# Ultrasonic_mbed.net
KiCad netlist of a schematic drawn in Altium Designer
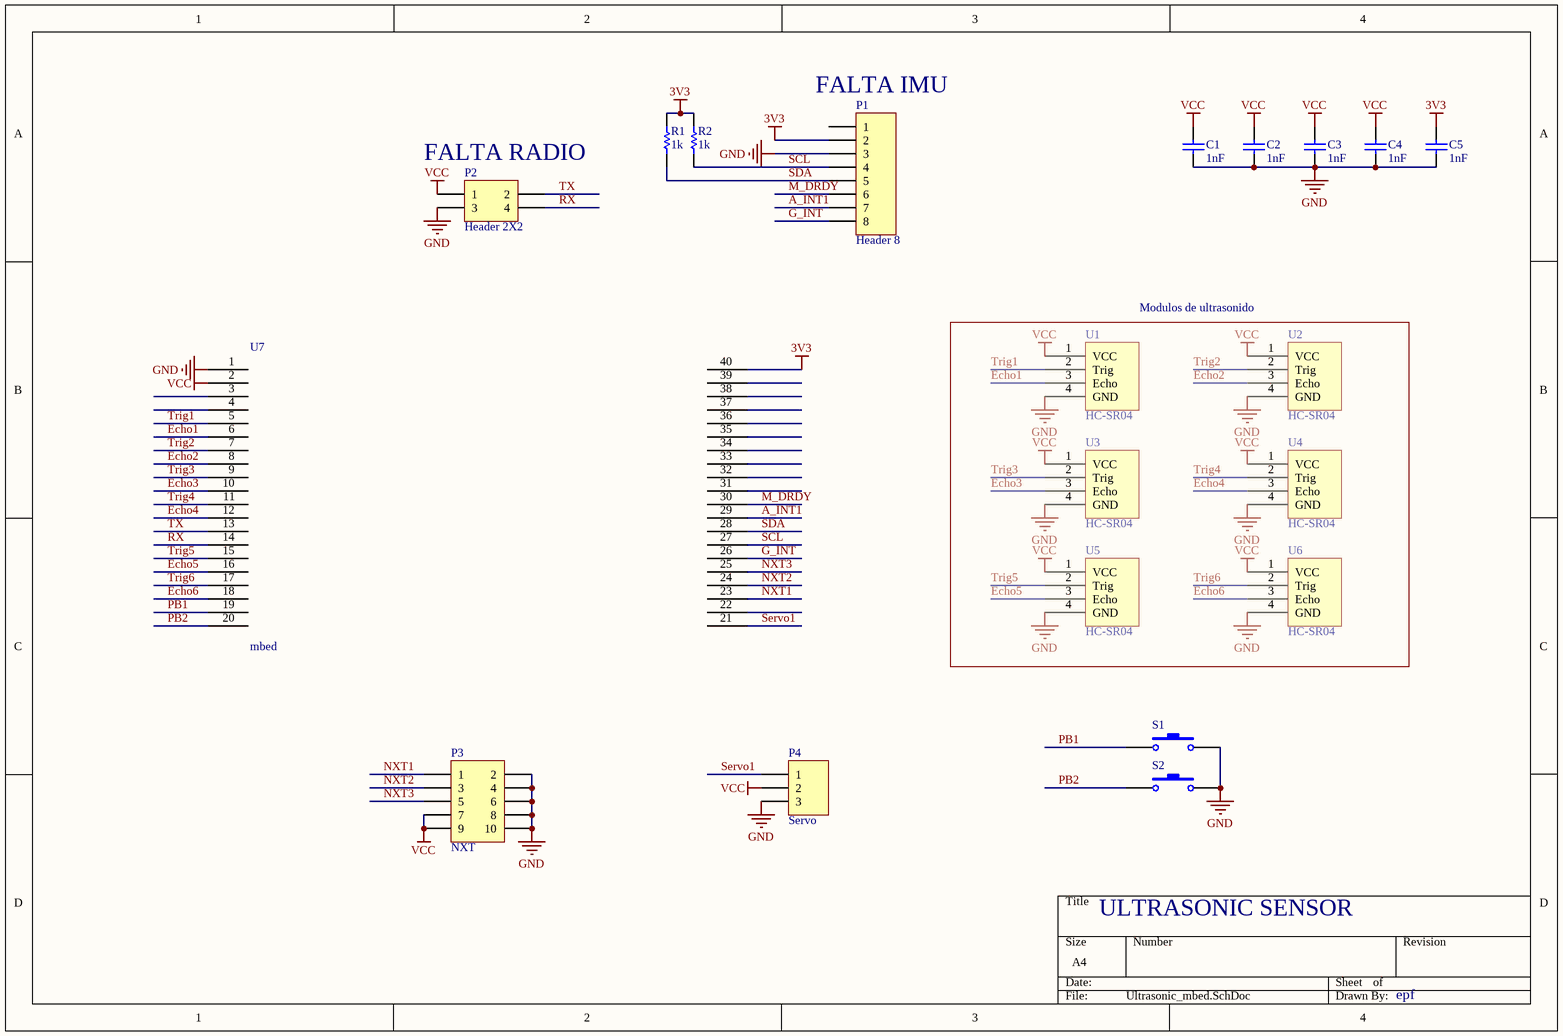
[diagram p0: Ultrasonic_mbed.SchDoc]

(export (version "E")
  (design (tool "Eeschema 10.0.6"))
  (components
    (comp (ref "C1")
      (value "1nF")
      (footprint "CAP0805")
      (fields (field (name "Comment") "Capacitor"))
      (libsource (lib "epf") (part "Cap"))
    )
    (comp (ref "C2")
      (value "1nF")
      (footprint "CAP0805")
      (fields (field (name "Comment") "Capacitor"))
      (libsource (lib "epf") (part "Cap"))
    )
    (comp (ref "C3")
      (value "1nF")
      (footprint "CAP0805")
      (fields (field (name "Comment") "Capacitor"))
      (libsource (lib "epf") (part "Cap"))
    )
    (comp (ref "C4")
      (value "1nF")
      (footprint "CAP0805")
      (fields (field (name "Comment") "Capacitor"))
      (libsource (lib "epf") (part "Cap"))
    )
    (comp (ref "C5")
      (value "1nF")
      (footprint "CAP0805")
      (fields (field (name "Comment") "Capacitor"))
      (libsource (lib "epf") (part "Cap"))
    )
    (comp (ref "P1")
      (value "Header 8")
      (footprint "HDR1X8")
      (description "Header, 8-Pin")
      (fields (field (name "PUBLISHER") "Altium Limited"))
      (libsource (lib "Miscellaneous Connectors") (part "Header 8"))
    )
    (comp (ref "P2")
      (value "Header 2X2")
      (footprint "HDR2X2")
      (description "Header, 2-Pin, Dual row")
      (fields (field (name "PUBLISHER") "Altium Limited"))
      (libsource (lib "Miscellaneous Connectors") (part "Header 2X2"))
    )
    (comp (ref "P3")
      (value "NXT")
      (footprint "HDR2X5")
      (description "Header, 5-Pin, Dual row")
      (fields (field (name "PUBLISHER") "Altium Limited"))
      (libsource (lib "epf") (part "Header 5X2"))
    )
    (comp (ref "P4")
      (value "Servo")
      (footprint "HDR1X3")
      (description "Header, 3-Pin")
      (fields (field (name "PUBLISHER") "Altium Limited"))
      (libsource (lib "Miscellaneous Connectors") (part "Header 3"))
    )
    (comp (ref "R1")
      (value "1k")
      (footprint "RES0805")
      (fields (field (name "Comment") "Resistor"))
      (libsource (lib "epf") (part "Res"))
    )
    (comp (ref "R2")
      (value "1k")
      (footprint "RES0805")
      (fields (field (name "Comment") "Resistor"))
      (libsource (lib "epf") (part "Res"))
    )
    (comp (ref "S1")
      (value "SW-PB")
      (footprint "SW-PB6mm - 2")
      (description "Switch")
      (fields (field (name "PUBLISHER") "Altium Limited"))
      (libsource (lib "epf") (part "SW-PB"))
    )
    (comp (ref "S2")
      (value "SW-PB")
      (footprint "SW-PB6mm - 2")
      (description "Switch")
      (fields (field (name "PUBLISHER") "Altium Limited"))
      (libsource (lib "epf") (part "SW-PB"))
    )
    (comp (ref "U1")
      (value "HC-SR04")
      (footprint "HC-SR04")
      (description "Ultrasonic module")
      (libsource (lib "epf") (part "HC-SR04"))
    )
    (comp (ref "U2")
      (value "HC-SR04")
      (footprint "HC-SR04")
      (description "Ultrasonic module")
      (libsource (lib "epf") (part "HC-SR04"))
    )
    (comp (ref "U3")
      (value "HC-SR04")
      (footprint "HC-SR04")
      (description "Ultrasonic module")
      (libsource (lib "epf") (part "HC-SR04"))
    )
    (comp (ref "U4")
      (value "HC-SR04")
      (footprint "HC-SR04")
      (description "Ultrasonic module")
      (libsource (lib "epf") (part "HC-SR04"))
    )
    (comp (ref "U5")
      (value "HC-SR04")
      (footprint "HC-SR04")
      (description "Ultrasonic module")
      (libsource (lib "epf") (part "HC-SR04"))
    )
    (comp (ref "U6")
      (value "HC-SR04")
      (footprint "HC-SR04")
      (description "Ultrasonic module")
      (libsource (lib "epf") (part "HC-SR04"))
    )
    (comp (ref "U7") (value "mbed") (footprint "mbed") (libsource (lib "epf") (part "mbed")))
  )
  (nets
    (net (code "1") (name "/A_INT1") (class "Default")
      (node (ref "P1") (pin "7") (pinfunction "7_7") (pintype "passive"))
      (node (ref "U7") (pin "29") (pinfunction "29_29") (pintype "passive"))
    )
    (net (code "2") (name "/Echo1") (class "Default")
      (node (ref "U1") (pin "3") (pinfunction "Echo_3") (pintype "passive"))
      (node (ref "U7") (pin "6") (pinfunction "6_6") (pintype "passive"))
    )
    (net (code "3") (name "/Echo2") (class "Default")
      (node (ref "U2") (pin "3") (pinfunction "Echo_3") (pintype "passive"))
      (node (ref "U7") (pin "8") (pinfunction "8_8") (pintype "passive"))
    )
    (net (code "4") (name "/Echo3") (class "Default")
      (node (ref "U3") (pin "3") (pinfunction "Echo_3") (pintype "passive"))
      (node (ref "U7") (pin "10") (pinfunction "10_10") (pintype "passive"))
    )
    (net (code "5") (name "/Echo4") (class "Default")
      (node (ref "U4") (pin "3") (pinfunction "Echo_3") (pintype "passive"))
      (node (ref "U7") (pin "12") (pinfunction "12_12") (pintype "passive"))
    )
    (net (code "6") (name "/Echo5") (class "Default")
      (node (ref "U5") (pin "3") (pinfunction "Echo_3") (pintype "passive"))
      (node (ref "U7") (pin "16") (pinfunction "16_16") (pintype "passive"))
    )
    (net (code "7") (name "/Echo6") (class "Default")
      (node (ref "U6") (pin "3") (pinfunction "Echo_3") (pintype "passive"))
      (node (ref "U7") (pin "18") (pinfunction "18_18") (pintype "passive"))
    )
    (net (code "8") (name "/G_INT") (class "Default")
      (node (ref "P1") (pin "8") (pinfunction "8_8") (pintype "passive"))
      (node (ref "U7") (pin "26") (pinfunction "26_26") (pintype "passive"))
    )
    (net (code "9") (name "/M_DRDY") (class "Default")
      (node (ref "P1") (pin "6") (pinfunction "6_6") (pintype "passive"))
      (node (ref "U7") (pin "30") (pinfunction "30_30") (pintype "passive"))
    )
    (net (code "10") (name "/NXT1") (class "Default")
      (node (ref "P3") (pin "1") (pinfunction "1_1") (pintype "passive"))
      (node (ref "U7") (pin "23") (pinfunction "23_23") (pintype "passive"))
    )
    (net (code "11") (name "/NXT2") (class "Default")
      (node (ref "P3") (pin "3") (pinfunction "3_3") (pintype "passive"))
      (node (ref "U7") (pin "24") (pinfunction "24_24") (pintype "passive"))
    )
    (net (code "12") (name "/NXT3") (class "Default")
      (node (ref "P3") (pin "5") (pinfunction "5_5") (pintype "passive"))
      (node (ref "U7") (pin "25") (pinfunction "25_25") (pintype "passive"))
    )
    (net (code "13") (name "/PB1") (class "Default")
      (node (ref "S1") (pin "1") (pinfunction "1_1") (pintype "passive"))
      (node (ref "U7") (pin "19") (pinfunction "19_19") (pintype "passive"))
    )
    (net (code "14") (name "/PB2") (class "Default")
      (node (ref "S2") (pin "1") (pinfunction "1_1") (pintype "passive"))
      (node (ref "U7") (pin "20") (pinfunction "20_20") (pintype "passive"))
    )
    (net (code "15") (name "/RX") (class "Default")
      (node (ref "P2") (pin "4") (pinfunction "4_4") (pintype "passive"))
      (node (ref "U7") (pin "14") (pinfunction "14_14") (pintype "passive"))
    )
    (net (code "16") (name "/SCL") (class "Default")
      (node (ref "P1") (pin "4") (pinfunction "4_4") (pintype "passive"))
      (node (ref "R2") (pin "2") (pinfunction "2_2") (pintype "passive"))
      (node (ref "U7") (pin "27") (pinfunction "27_27") (pintype "passive"))
    )
    (net (code "17") (name "/SDA") (class "Default")
      (node (ref "P1") (pin "5") (pinfunction "5_5") (pintype "passive"))
      (node (ref "R1") (pin "2") (pinfunction "2_2") (pintype "passive"))
      (node (ref "U7") (pin "28") (pinfunction "28_28") (pintype "passive"))
    )
    (net (code "18") (name "/Servo1") (class "Default")
      (node (ref "P4") (pin "1") (pinfunction "1_1") (pintype "passive"))
      (node (ref "U7") (pin "21") (pinfunction "21_21") (pintype "passive"))
    )
    (net (code "19") (name "/TX") (class "Default")
      (node (ref "P2") (pin "2") (pinfunction "2_2") (pintype "passive"))
      (node (ref "U7") (pin "13") (pinfunction "13_13") (pintype "passive"))
    )
    (net (code "20") (name "/Trig1") (class "Default")
      (node (ref "U1") (pin "2") (pinfunction "Trig_2") (pintype "passive"))
      (node (ref "U7") (pin "5") (pinfunction "5_5") (pintype "passive"))
    )
    (net (code "21") (name "/Trig2") (class "Default")
      (node (ref "U2") (pin "2") (pinfunction "Trig_2") (pintype "passive"))
      (node (ref "U7") (pin "7") (pinfunction "7_7") (pintype "passive"))
    )
    (net (code "22") (name "/Trig3") (class "Default")
      (node (ref "U3") (pin "2") (pinfunction "Trig_2") (pintype "passive"))
      (node (ref "U7") (pin "9") (pinfunction "9_9") (pintype "passive"))
    )
    (net (code "23") (name "/Trig4") (class "Default")
      (node (ref "U4") (pin "2") (pinfunction "Trig_2") (pintype "passive"))
      (node (ref "U7") (pin "11") (pinfunction "11_11") (pintype "passive"))
    )
    (net (code "24") (name "/Trig5") (class "Default")
      (node (ref "U5") (pin "2") (pinfunction "Trig_2") (pintype "passive"))
      (node (ref "U7") (pin "15") (pinfunction "15_15") (pintype "passive"))
    )
    (net (code "25") (name "/Trig6") (class "Default")
      (node (ref "U6") (pin "2") (pinfunction "Trig_2") (pintype "passive"))
      (node (ref "U7") (pin "17") (pinfunction "17_17") (pintype "passive"))
    )
    (net (code "26") (name "3V3") (class "Default")
      (node (ref "C5") (pin "2") (pinfunction "2_2") (pintype "passive"))
      (node (ref "P1") (pin "2") (pinfunction "2_2") (pintype "passive"))
      (node (ref "R1") (pin "1") (pinfunction "1_1") (pintype "passive"))
      (node (ref "R2") (pin "1") (pinfunction "1_1") (pintype "passive"))
      (node (ref "U7") (pin "40") (pinfunction "40_40") (pintype "passive"))
    )
    (net (code "27") (name "GND") (class "Default")
      (node (ref "C1") (pin "1") (pinfunction "1_1") (pintype "passive"))
      (node (ref "C2") (pin "1") (pinfunction "1_1") (pintype "passive"))
      (node (ref "C3") (pin "1") (pinfunction "1_1") (pintype "passive"))
      (node (ref "C4") (pin "1") (pinfunction "1_1") (pintype "passive"))
      (node (ref "C5") (pin "1") (pinfunction "1_1") (pintype "passive"))
      (node (ref "P1") (pin "3") (pinfunction "3_3") (pintype "passive"))
      (node (ref "P2") (pin "3") (pinfunction "3_3") (pintype "passive"))
      (node (ref "P3") (pin "10") (pinfunction "10_10") (pintype "passive"))
      (node (ref "P3") (pin "2") (pinfunction "2_2") (pintype "passive"))
      (node (ref "P3") (pin "4") (pinfunction "4_4") (pintype "passive"))
      (node (ref "P3") (pin "6") (pinfunction "6_6") (pintype "passive"))
      (node (ref "P3") (pin "8") (pinfunction "8_8") (pintype "passive"))
      (node (ref "P4") (pin "3") (pinfunction "3_3") (pintype "passive"))
      (node (ref "S1") (pin "2") (pinfunction "2_2") (pintype "passive"))
      (node (ref "S2") (pin "2") (pinfunction "2_2") (pintype "passive"))
      (node (ref "U1") (pin "4") (pinfunction "GND_4") (pintype "passive"))
      (node (ref "U2") (pin "4") (pinfunction "GND_4") (pintype "passive"))
      (node (ref "U3") (pin "4") (pinfunction "GND_4") (pintype "passive"))
      (node (ref "U4") (pin "4") (pinfunction "GND_4") (pintype "passive"))
      (node (ref "U5") (pin "4") (pinfunction "GND_4") (pintype "passive"))
      (node (ref "U6") (pin "4") (pinfunction "GND_4") (pintype "passive"))
      (node (ref "U7") (pin "1") (pinfunction "1_1") (pintype "passive"))
    )
    (net (code "28") (name "VCC") (class "Default")
      (node (ref "C1") (pin "2") (pinfunction "2_2") (pintype "passive"))
      (node (ref "C2") (pin "2") (pinfunction "2_2") (pintype "passive"))
      (node (ref "C3") (pin "2") (pinfunction "2_2") (pintype "passive"))
      (node (ref "C4") (pin "2") (pinfunction "2_2") (pintype "passive"))
      (node (ref "P2") (pin "1") (pinfunction "1_1") (pintype "passive"))
      (node (ref "P3") (pin "7") (pinfunction "7_7") (pintype "passive"))
      (node (ref "P3") (pin "9") (pinfunction "9_9") (pintype "passive"))
      (node (ref "P4") (pin "2") (pinfunction "2_2") (pintype "passive"))
      (node (ref "U1") (pin "1") (pinfunction "VCC_1") (pintype "passive"))
      (node (ref "U2") (pin "1") (pinfunction "VCC_1") (pintype "passive"))
      (node (ref "U3") (pin "1") (pinfunction "VCC_1") (pintype "passive"))
      (node (ref "U4") (pin "1") (pinfunction "VCC_1") (pintype "passive"))
      (node (ref "U5") (pin "1") (pinfunction "VCC_1") (pintype "passive"))
      (node (ref "U6") (pin "1") (pinfunction "VCC_1") (pintype "passive"))
      (node (ref "U7") (pin "2") (pinfunction "2_2") (pintype "passive"))
    )
    (net (code "29") (name "unconnected-(P1-Pad1)") (class "Default")
      (node (ref "P1") (pin "1") (pinfunction "1_1") (pintype "passive"))
    )
    (net (code "30") (name "unconnected-(U7-Pad3)") (class "Default")
      (node (ref "U7") (pin "3") (pinfunction "3_3") (pintype "passive"))
    )
    (net (code "31") (name "unconnected-(U7-Pad4)") (class "Default")
      (node (ref "U7") (pin "4") (pinfunction "4_4") (pintype "passive"))
    )
    (net (code "32") (name "unconnected-(U7-Pad22)") (class "Default")
      (node (ref "U7") (pin "22") (pinfunction "22_22") (pintype "passive"))
    )
    (net (code "33") (name "unconnected-(U7-Pad31)") (class "Default")
      (node (ref "U7") (pin "31") (pinfunction "31_31") (pintype "passive"))
    )
    (net (code "34") (name "unconnected-(U7-Pad32)") (class "Default")
      (node (ref "U7") (pin "32") (pinfunction "32_32") (pintype "passive"))
    )
    (net (code "35") (name "unconnected-(U7-Pad33)") (class "Default")
      (node (ref "U7") (pin "33") (pinfunction "33_33") (pintype "passive"))
    )
    (net (code "36") (name "unconnected-(U7-Pad34)") (class "Default")
      (node (ref "U7") (pin "34") (pinfunction "34_34") (pintype "passive"))
    )
    (net (code "37") (name "unconnected-(U7-Pad35)") (class "Default")
      (node (ref "U7") (pin "35") (pinfunction "35_35") (pintype "passive"))
    )
    (net (code "38") (name "unconnected-(U7-Pad36)") (class "Default")
      (node (ref "U7") (pin "36") (pinfunction "36_36") (pintype "passive"))
    )
    (net (code "39") (name "unconnected-(U7-Pad37)") (class "Default")
      (node (ref "U7") (pin "37") (pinfunction "37_37") (pintype "passive"))
    )
    (net (code "40") (name "unconnected-(U7-Pad38)") (class "Default")
      (node (ref "U7") (pin "38") (pinfunction "38_38") (pintype "passive"))
    )
    (net (code "41") (name "unconnected-(U7-Pad39)") (class "Default")
      (node (ref "U7") (pin "39") (pinfunction "39_39") (pintype "passive"))
    )
  )
)
